# montaj_electric.net
KiCad netlist of a schematic drawn in EAGLE
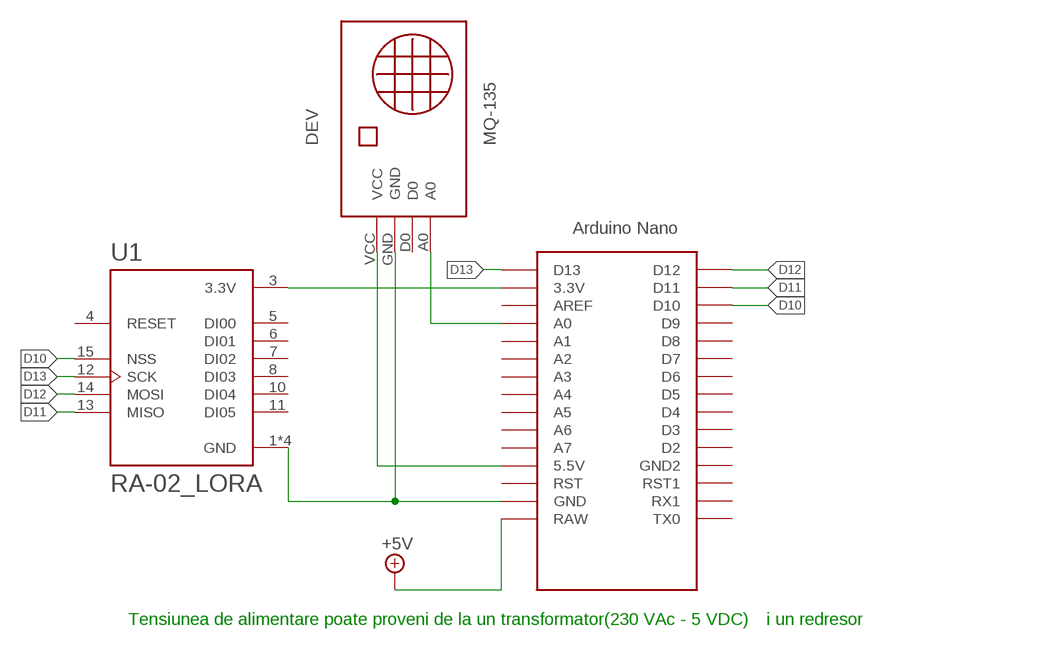
[diagram p0: schematic, sheet 1]

(export (version "E")
  (design (tool "Eeschema 10.0.6"))
  (components
    (comp (ref "U$1")
      (value "NANO")
      (footprint "eagle-import:NANO")
      (libsource (lib "eagle-import") (part "NANO"))
    )
    (comp (ref "U$2")
      (value "DEV")
      (footprint "eagle-import:FOOT")
      (libsource (lib "eagle-import") (part "DEV"))
    )
    (comp (ref "U1")
      (value "RA-02_LORA")
      (footprint "eagle-import:MODULE_RA-02_LORA")
      (fields (field (name "MF") "AI-Thinker") (field (name "MP") "Ra-02 LoRa"))
      (libsource (lib "eagle-import") (part "RA-02_LORA"))
    )
  )
  (nets
    (net (code "1") (name "+5V") (class "Default")
      (node (ref "U$1") (pin "RAW") (pinfunction "RAW_RAW") (pintype "bidirectional"))
    )
    (net (code "2") (name "D10") (class "Default")
      (node (ref "U$1") (pin "D10") (pinfunction "D10_D10") (pintype "bidirectional"))
      (node (ref "U1") (pin "15") (pinfunction "NSS_15") (pintype "input"))
    )
    (net (code "3") (name "D11") (class "Default")
      (node (ref "U$1") (pin "D11") (pinfunction "D11_D11") (pintype "bidirectional"))
      (node (ref "U1") (pin "13") (pinfunction "MISO_13") (pintype "output"))
    )
    (net (code "4") (name "D12") (class "Default")
      (node (ref "U$1") (pin "D12") (pinfunction "D12_D12") (pintype "bidirectional"))
      (node (ref "U1") (pin "14") (pinfunction "MOSI_14") (pintype "input"))
    )
    (net (code "5") (name "D13") (class "Default")
      (node (ref "U$1") (pin "D13") (pinfunction "D13_D13") (pintype "bidirectional"))
      (node (ref "U1") (pin "12") (pinfunction "SCK_12") (pintype "input"))
    )
    (net (code "6") (name "Net-(U$1-5.5V)") (class "Default")
      (node (ref "U$1") (pin "5V") (pinfunction "5.5V_5V") (pintype "bidirectional"))
      (node (ref "U$2") (pin "VCC") (pinfunction "VCC_VCC") (pintype "bidirectional"))
    )
    (net (code "7") (name "Net-(U$1-PadA0)") (class "Default")
      (node (ref "U$1") (pin "A0") (pinfunction "A0_A0") (pintype "bidirectional"))
      (node (ref "U$2") (pin "A0") (pinfunction "A0_A0") (pintype "bidirectional"))
    )
    (net (code "8") (name "Net-(U$1-PadGND)") (class "Default")
      (node (ref "U$1") (pin "GND") (pinfunction "GND_GND") (pintype "bidirectional"))
      (node (ref "U$2") (pin "GND") (pinfunction "GND_GND") (pintype "bidirectional"))
      (node (ref "U1") (pin "1") (pinfunction "GND_1") (pintype "power_in"))
      (node (ref "U1") (pin "16") (pinfunction "GND_16") (pintype "power_in"))
      (node (ref "U1") (pin "2") (pinfunction "GND_2") (pintype "power_in"))
      (node (ref "U1") (pin "9") (pinfunction "GND_9") (pintype "power_in"))
    )
    (net (code "9") (name "Net-(U1-3.3V)") (class "Default")
      (node (ref "U$1") (pin "3.3V") (pinfunction "3.3V_3.3V") (pintype "bidirectional"))
      (node (ref "U1") (pin "3") (pinfunction "3.3V_3") (pintype "power_in"))
    )
    (net (code "10") (name "unconnected-(U$1-GND2-PadGND1)") (class "Default")
      (node (ref "U$1") (pin "GND1") (pinfunction "GND2_GND1") (pintype "bidirectional"))
    )
    (net (code "11") (name "unconnected-(U$1-PadA1)") (class "Default")
      (node (ref "U$1") (pin "A1") (pinfunction "A1_A1") (pintype "bidirectional"))
    )
    (net (code "12") (name "unconnected-(U$1-PadA2)") (class "Default")
      (node (ref "U$1") (pin "A2") (pinfunction "A2_A2") (pintype "bidirectional"))
    )
    (net (code "13") (name "unconnected-(U$1-PadA3)") (class "Default")
      (node (ref "U$1") (pin "A3") (pinfunction "A3_A3") (pintype "bidirectional"))
    )
    (net (code "14") (name "unconnected-(U$1-PadA4)") (class "Default")
      (node (ref "U$1") (pin "A4") (pinfunction "A4_A4") (pintype "bidirectional"))
    )
    (net (code "15") (name "unconnected-(U$1-PadA5)") (class "Default")
      (node (ref "U$1") (pin "A5") (pinfunction "A5_A5") (pintype "bidirectional"))
    )
    (net (code "16") (name "unconnected-(U$1-PadA6)") (class "Default")
      (node (ref "U$1") (pin "A6") (pinfunction "A6_A6") (pintype "bidirectional"))
    )
    (net (code "17") (name "unconnected-(U$1-PadA7)") (class "Default")
      (node (ref "U$1") (pin "A7") (pinfunction "A7_A7") (pintype "bidirectional"))
    )
    (net (code "18") (name "unconnected-(U$1-PadAREF)") (class "Default")
      (node (ref "U$1") (pin "AREF") (pinfunction "AREF_AREF") (pintype "bidirectional"))
    )
    (net (code "19") (name "unconnected-(U$1-PadD2)") (class "Default")
      (node (ref "U$1") (pin "D2") (pinfunction "D2_D2") (pintype "bidirectional"))
    )
    (net (code "20") (name "unconnected-(U$1-PadD3)") (class "Default")
      (node (ref "U$1") (pin "D3") (pinfunction "D3_D3") (pintype "bidirectional"))
    )
    (net (code "21") (name "unconnected-(U$1-PadD4)") (class "Default")
      (node (ref "U$1") (pin "D4") (pinfunction "D4_D4") (pintype "bidirectional"))
    )
    (net (code "22") (name "unconnected-(U$1-PadD5)") (class "Default")
      (node (ref "U$1") (pin "D5") (pinfunction "D5_D5") (pintype "bidirectional"))
    )
    (net (code "23") (name "unconnected-(U$1-PadD6)") (class "Default")
      (node (ref "U$1") (pin "D6") (pinfunction "D6_D6") (pintype "bidirectional"))
    )
    (net (code "24") (name "unconnected-(U$1-PadD7)") (class "Default")
      (node (ref "U$1") (pin "D7") (pinfunction "D7_D7") (pintype "bidirectional"))
    )
    (net (code "25") (name "unconnected-(U$1-PadD8)") (class "Default")
      (node (ref "U$1") (pin "D8") (pinfunction "D8_D8") (pintype "bidirectional"))
    )
    (net (code "26") (name "unconnected-(U$1-PadD9)") (class "Default")
      (node (ref "U$1") (pin "D9") (pinfunction "D9_D9") (pintype "bidirectional"))
    )
    (net (code "27") (name "unconnected-(U$1-PadICSP1)") (class "Default")
      (node (ref "U$1") (pin "ICSP1") (pinfunction "ICSP1_ICSP1") (pintype "bidirectional"))
    )
    (net (code "28") (name "unconnected-(U$1-PadICSP2)") (class "Default")
      (node (ref "U$1") (pin "ICSP2") (pinfunction "ICSP2_ICSP2") (pintype "bidirectional"))
    )
    (net (code "29") (name "unconnected-(U$1-PadICSP3)") (class "Default")
      (node (ref "U$1") (pin "ICSP3") (pinfunction "ICSP3_ICSP3") (pintype "bidirectional"))
    )
    (net (code "30") (name "unconnected-(U$1-PadICSP4)") (class "Default")
      (node (ref "U$1") (pin "ICSP4") (pinfunction "ICSP4_ICSP4") (pintype "bidirectional"))
    )
    (net (code "31") (name "unconnected-(U$1-PadICSP5)") (class "Default")
      (node (ref "U$1") (pin "ICSP5") (pinfunction "ICSP5_ICSP5") (pintype "bidirectional"))
    )
    (net (code "32") (name "unconnected-(U$1-PadICSP6)") (class "Default")
      (node (ref "U$1") (pin "ICSP6") (pinfunction "ICSP6_ICSP6") (pintype "bidirectional"))
    )
    (net (code "33") (name "unconnected-(U$1-PadRST)") (class "Default")
      (node (ref "U$1") (pin "RST") (pinfunction "RST_RST") (pintype "bidirectional"))
    )
    (net (code "34") (name "unconnected-(U$1-PadRST1)") (class "Default")
      (node (ref "U$1") (pin "RST1") (pinfunction "RST1_RST1") (pintype "bidirectional"))
    )
    (net (code "35") (name "unconnected-(U$1-PadRX1)") (class "Default")
      (node (ref "U$1") (pin "RX1") (pinfunction "RX1_RX1") (pintype "bidirectional"))
    )
    (net (code "36") (name "unconnected-(U$1-PadTX0)") (class "Default")
      (node (ref "U$1") (pin "TX0") (pinfunction "TX0_TX0") (pintype "bidirectional"))
    )
    (net (code "37") (name "unconnected-(U$2-PadD0)") (class "Default")
      (node (ref "U$2") (pin "D0") (pinfunction "D0_D0") (pintype "bidirectional"))
    )
    (net (code "38") (name "unconnected-(U1-DI00-Pad5)") (class "Default")
      (node (ref "U1") (pin "5") (pinfunction "DI00_5") (pintype "bidirectional"))
    )
    (net (code "39") (name "unconnected-(U1-DI01-Pad6)") (class "Default")
      (node (ref "U1") (pin "6") (pinfunction "DI01_6") (pintype "bidirectional"))
    )
    (net (code "40") (name "unconnected-(U1-DI02-Pad7)") (class "Default")
      (node (ref "U1") (pin "7") (pinfunction "DI02_7") (pintype "bidirectional"))
    )
    (net (code "41") (name "unconnected-(U1-DI03-Pad8)") (class "Default")
      (node (ref "U1") (pin "8") (pinfunction "DI03_8") (pintype "bidirectional"))
    )
    (net (code "42") (name "unconnected-(U1-DI04-Pad10)") (class "Default")
      (node (ref "U1") (pin "10") (pinfunction "DI04_10") (pintype "bidirectional"))
    )
    (net (code "43") (name "unconnected-(U1-DI05-Pad11)") (class "Default")
      (node (ref "U1") (pin "11") (pinfunction "DI05_11") (pintype "bidirectional"))
    )
    (net (code "44") (name "unconnected-(U1-RESET-Pad4)") (class "Default")
      (node (ref "U1") (pin "4") (pinfunction "RESET_4") (pintype "input"))
    )
  )
)
